# SCH_AquaMind_2026-07-25.net
KiCad netlist of a schematic drawn in EasyEDA
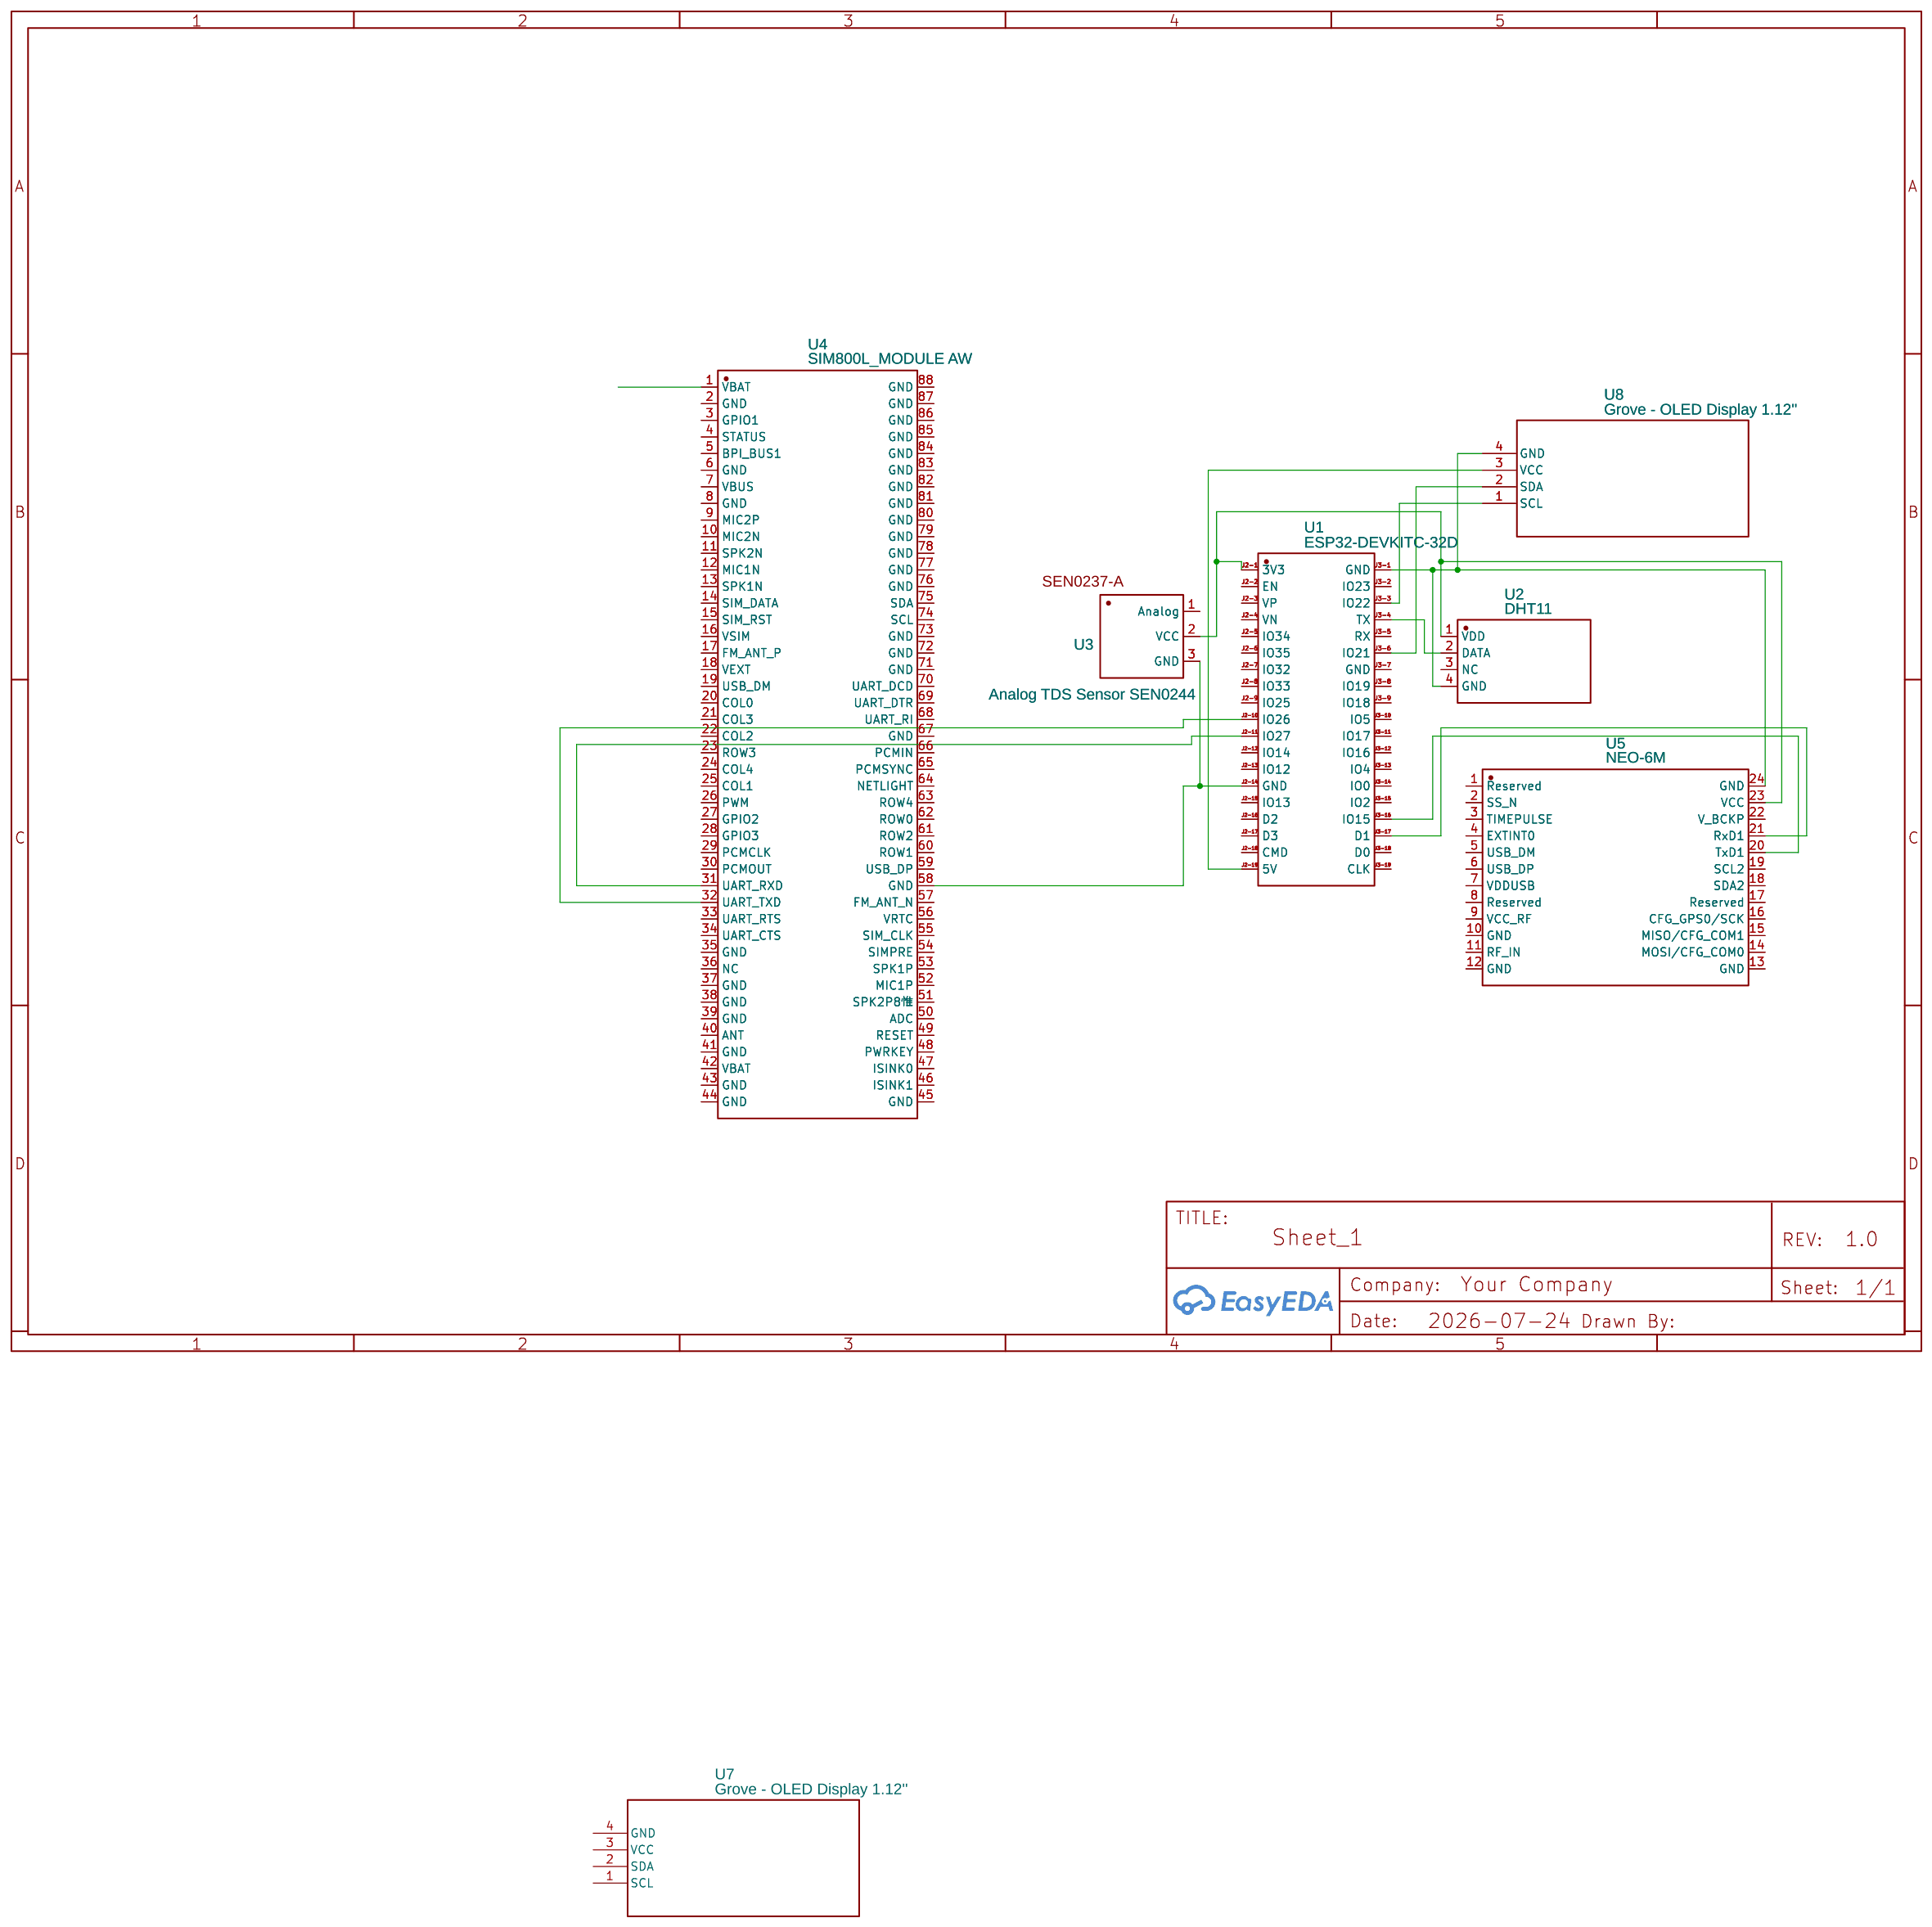
[diagram p0: schematic sheet]

(export (version "E")
  (design (tool "Eeschema 10.0.6"))
  (components
    (comp (ref "U1")
      (value "ESP32-DEVKITC-32D")
      (fields
        (field (name "Manufacturer Part") "ESP32-DevKitC-32D")
        (field (name "Manufacturer") "ESPRESSIF(乐鑫)")
      )
      (libsource (lib "") (part "ESP32-DEVKITC-32D"))
    )
    (comp (ref "U2")
      (value "DHT11")
      (fields (field (name "Manufacturer") "广州奥松"))
      (libsource (lib "") (part "DHT11"))
    )
    (comp (ref "U3")
      (value "Analog TDS Sensor SEN0244")
      (libsource (lib "") (part "Analog TDS Sensor SEN0244"))
    )
    (comp (ref "U4") (value "SIM800L_MODULE AW") (libsource (lib "") (part "SIM800L_MODULE AW")))
    (comp (ref "U5") (value "NEO-6M") (libsource (lib "") (part "NEO-6M")))
    (comp (ref "U7")
      (value "Grove - OLED Display 1.12''")
      (libsource (lib "") (part "Grove - OLED Display 1.12''"))
    )
    (comp (ref "U8")
      (value "Grove - OLED Display 1.12''")
      (libsource (lib "") (part "Grove - OLED Display 1.12''"))
    )
  )
  (nets
    (net (code "1") (name "Net-(U1-3V3)") (class "Default")
      (node (ref "U1") (pin "J2-1") (pinfunction "3V3_J2-1") (pintype "unspecified"))
      (node (ref "U2") (pin "1") (pinfunction "VDD_1") (pintype "unspecified"))
      (node (ref "U3") (pin "2") (pinfunction "VCC_2") (pintype "unspecified"))
      (node (ref "U5") (pin "23") (pinfunction "VCC_23") (pintype "unspecified"))
    )
    (net (code "2") (name "Net-(U1-5V)") (class "Default")
      (node (ref "U1") (pin "J2-19") (pinfunction "5V_J2-19") (pintype "unspecified"))
      (node (ref "U8") (pin "3") (pinfunction "VCC_3") (pintype "unspecified"))
    )
    (net (code "3") (name "Net-(U1-D1)") (class "Default")
      (node (ref "U1") (pin "J3-17") (pinfunction "D1_J3-17") (pintype "unspecified"))
      (node (ref "U5") (pin "21") (pinfunction "RxD1_21") (pintype "unspecified"))
    )
    (net (code "4") (name "Net-(U1-IO15)") (class "Default")
      (node (ref "U1") (pin "J3-16") (pinfunction "IO15_J3-16") (pintype "unspecified"))
      (node (ref "U5") (pin "20") (pinfunction "TxD1_20") (pintype "unspecified"))
    )
    (net (code "5") (name "Net-(U1-IO21)") (class "Default")
      (node (ref "U1") (pin "J3-6") (pinfunction "IO21_J3-6") (pintype "unspecified"))
      (node (ref "U8") (pin "2") (pinfunction "SDA_2") (pintype "unspecified"))
    )
    (net (code "6") (name "Net-(U1-IO22)") (class "Default")
      (node (ref "U1") (pin "J3-3") (pinfunction "IO22_J3-3") (pintype "unspecified"))
      (node (ref "U8") (pin "1") (pinfunction "SCL_1") (pintype "unspecified"))
    )
    (net (code "7") (name "Net-(U1-IO26)") (class "Default")
      (node (ref "U1") (pin "J2-10") (pinfunction "IO26_J2-10") (pintype "unspecified"))
      (node (ref "U4") (pin "32") (pinfunction "UART_TXD_32") (pintype "unspecified"))
    )
    (net (code "8") (name "Net-(U1-IO27)") (class "Default")
      (node (ref "U1") (pin "J2-11") (pinfunction "IO27_J2-11") (pintype "unspecified"))
      (node (ref "U4") (pin "31") (pinfunction "UART_RXD_31") (pintype "unspecified"))
    )
    (net (code "9") (name "Net-(U1-TX)") (class "Default")
      (node (ref "U1") (pin "J3-4") (pinfunction "TX_J3-4") (pintype "unspecified"))
      (node (ref "U2") (pin "2") (pinfunction "DATA_2") (pintype "unspecified"))
    )
    (net (code "10") (name "Net-(U2-GND)") (class "Default")
      (node (ref "U1") (pin "J3-1") (pinfunction "GND_J3-1") (pintype "unspecified"))
      (node (ref "U2") (pin "4") (pinfunction "GND_4") (pintype "unspecified"))
      (node (ref "U5") (pin "24") (pinfunction "GND_24") (pintype "unspecified"))
      (node (ref "U8") (pin "4") (pinfunction "GND_4") (pintype "unspecified"))
    )
    (net (code "11") (name "Net-(U3-GND)") (class "Default")
      (node (ref "U1") (pin "J2-14") (pinfunction "GND_J2-14") (pintype "unspecified"))
      (node (ref "U3") (pin "3") (pinfunction "GND_3") (pintype "unspecified"))
      (node (ref "U4") (pin "58") (pinfunction "GND_58") (pintype "unspecified"))
    )
    (net (code "12") (name "unconnected-(U1-CLK-PadJ3-19)") (class "Default")
      (node (ref "U1") (pin "J3-19") (pinfunction "CLK_J3-19") (pintype "unspecified"))
    )
    (net (code "13") (name "unconnected-(U1-CMD-PadJ2-18)") (class "Default")
      (node (ref "U1") (pin "J2-18") (pinfunction "CMD_J2-18") (pintype "unspecified"))
    )
    (net (code "14") (name "unconnected-(U1-D0-PadJ3-18)") (class "Default")
      (node (ref "U1") (pin "J3-18") (pinfunction "D0_J3-18") (pintype "unspecified"))
    )
    (net (code "15") (name "unconnected-(U1-D2-PadJ2-16)") (class "Default")
      (node (ref "U1") (pin "J2-16") (pinfunction "D2_J2-16") (pintype "unspecified"))
    )
    (net (code "16") (name "unconnected-(U1-D3-PadJ2-17)") (class "Default")
      (node (ref "U1") (pin "J2-17") (pinfunction "D3_J2-17") (pintype "unspecified"))
    )
    (net (code "17") (name "unconnected-(U1-EN-PadJ2-2)") (class "Default")
      (node (ref "U1") (pin "J2-2") (pinfunction "EN_J2-2") (pintype "unspecified"))
    )
    (net (code "18") (name "unconnected-(U1-GND-PadJ3-7)") (class "Default")
      (node (ref "U1") (pin "J3-7") (pinfunction "GND_J3-7") (pintype "unspecified"))
    )
    (net (code "19") (name "unconnected-(U1-IO0-PadJ3-14)") (class "Default")
      (node (ref "U1") (pin "J3-14") (pinfunction "IO0_J3-14") (pintype "unspecified"))
    )
    (net (code "20") (name "unconnected-(U1-IO2-PadJ3-15)") (class "Default")
      (node (ref "U1") (pin "J3-15") (pinfunction "IO2_J3-15") (pintype "unspecified"))
    )
    (net (code "21") (name "unconnected-(U1-IO4-PadJ3-13)") (class "Default")
      (node (ref "U1") (pin "J3-13") (pinfunction "IO4_J3-13") (pintype "unspecified"))
    )
    (net (code "22") (name "unconnected-(U1-IO5-PadJ3-10)") (class "Default")
      (node (ref "U1") (pin "J3-10") (pinfunction "IO5_J3-10") (pintype "unspecified"))
    )
    (net (code "23") (name "unconnected-(U1-IO12-PadJ2-13)") (class "Default")
      (node (ref "U1") (pin "J2-13") (pinfunction "IO12_J2-13") (pintype "unspecified"))
    )
    (net (code "24") (name "unconnected-(U1-IO13-PadJ2-15)") (class "Default")
      (node (ref "U1") (pin "J2-15") (pinfunction "IO13_J2-15") (pintype "unspecified"))
    )
    (net (code "25") (name "unconnected-(U1-IO14-PadJ2-12)") (class "Default")
      (node (ref "U1") (pin "J2-12") (pinfunction "IO14_J2-12") (pintype "unspecified"))
    )
    (net (code "26") (name "unconnected-(U1-IO16-PadJ3-12)") (class "Default")
      (node (ref "U1") (pin "J3-12") (pinfunction "IO16_J3-12") (pintype "unspecified"))
    )
    (net (code "27") (name "unconnected-(U1-IO17-PadJ3-11)") (class "Default")
      (node (ref "U1") (pin "J3-11") (pinfunction "IO17_J3-11") (pintype "unspecified"))
    )
    (net (code "28") (name "unconnected-(U1-IO18-PadJ3-9)") (class "Default")
      (node (ref "U1") (pin "J3-9") (pinfunction "IO18_J3-9") (pintype "unspecified"))
    )
    (net (code "29") (name "unconnected-(U1-IO19-PadJ3-8)") (class "Default")
      (node (ref "U1") (pin "J3-8") (pinfunction "IO19_J3-8") (pintype "unspecified"))
    )
    (net (code "30") (name "unconnected-(U1-IO23-PadJ3-2)") (class "Default")
      (node (ref "U1") (pin "J3-2") (pinfunction "IO23_J3-2") (pintype "unspecified"))
    )
    (net (code "31") (name "unconnected-(U1-IO25-PadJ2-9)") (class "Default")
      (node (ref "U1") (pin "J2-9") (pinfunction "IO25_J2-9") (pintype "unspecified"))
    )
    (net (code "32") (name "unconnected-(U1-IO32-PadJ2-7)") (class "Default")
      (node (ref "U1") (pin "J2-7") (pinfunction "IO32_J2-7") (pintype "unspecified"))
    )
    (net (code "33") (name "unconnected-(U1-IO33-PadJ2-8)") (class "Default")
      (node (ref "U1") (pin "J2-8") (pinfunction "IO33_J2-8") (pintype "unspecified"))
    )
    (net (code "34") (name "unconnected-(U1-IO34-PadJ2-5)") (class "Default")
      (node (ref "U1") (pin "J2-5") (pinfunction "IO34_J2-5") (pintype "unspecified"))
    )
    (net (code "35") (name "unconnected-(U1-IO35-PadJ2-6)") (class "Default")
      (node (ref "U1") (pin "J2-6") (pinfunction "IO35_J2-6") (pintype "unspecified"))
    )
    (net (code "36") (name "unconnected-(U1-RX-PadJ3-5)") (class "Default")
      (node (ref "U1") (pin "J3-5") (pinfunction "RX_J3-5") (pintype "unspecified"))
    )
    (net (code "37") (name "unconnected-(U1-VN-PadJ2-4)") (class "Default")
      (node (ref "U1") (pin "J2-4") (pinfunction "VN_J2-4") (pintype "unspecified"))
    )
    (net (code "38") (name "unconnected-(U1-VP-PadJ2-3)") (class "Default")
      (node (ref "U1") (pin "J2-3") (pinfunction "VP_J2-3") (pintype "unspecified"))
    )
    (net (code "39") (name "unconnected-(U2-NC-Pad3)") (class "Default")
      (node (ref "U2") (pin "3") (pinfunction "NC_3") (pintype "unspecified"))
    )
    (net (code "40") (name "unconnected-(U3-Analog-Pad1)") (class "Default")
      (node (ref "U3") (pin "1") (pinfunction "Analog_1") (pintype "unspecified"))
    )
    (net (code "41") (name "unconnected-(U4-ADC-Pad50)") (class "Default")
      (node (ref "U4") (pin "50") (pinfunction "ADC_50") (pintype "unspecified"))
    )
    (net (code "42") (name "unconnected-(U4-ANT-Pad40)") (class "Default")
      (node (ref "U4") (pin "40") (pinfunction "ANT_40") (pintype "unspecified"))
    )
    (net (code "43") (name "unconnected-(U4-BPI_BUS1-Pad5)") (class "Default")
      (node (ref "U4") (pin "5") (pinfunction "BPI_BUS1_5") (pintype "unspecified"))
    )
    (net (code "44") (name "unconnected-(U4-COL0-Pad20)") (class "Default")
      (node (ref "U4") (pin "20") (pinfunction "COL0_20") (pintype "unspecified"))
    )
    (net (code "45") (name "unconnected-(U4-COL1-Pad25)") (class "Default")
      (node (ref "U4") (pin "25") (pinfunction "COL1_25") (pintype "unspecified"))
    )
    (net (code "46") (name "unconnected-(U4-COL2-Pad22)") (class "Default")
      (node (ref "U4") (pin "22") (pinfunction "COL2_22") (pintype "unspecified"))
    )
    (net (code "47") (name "unconnected-(U4-COL3-Pad21)") (class "Default")
      (node (ref "U4") (pin "21") (pinfunction "COL3_21") (pintype "unspecified"))
    )
    (net (code "48") (name "unconnected-(U4-COL4-Pad24)") (class "Default")
      (node (ref "U4") (pin "24") (pinfunction "COL4_24") (pintype "unspecified"))
    )
    (net (code "49") (name "unconnected-(U4-FM_ANT_N-Pad57)") (class "Default")
      (node (ref "U4") (pin "57") (pinfunction "FM_ANT_N_57") (pintype "unspecified"))
    )
    (net (code "50") (name "unconnected-(U4-FM_ANT_P-Pad17)") (class "Default")
      (node (ref "U4") (pin "17") (pinfunction "FM_ANT_P_17") (pintype "unspecified"))
    )
    (net (code "51") (name "unconnected-(U4-GND-Pad2)") (class "Default")
      (node (ref "U4") (pin "2") (pinfunction "GND_2") (pintype "unspecified"))
    )
    (net (code "52") (name "unconnected-(U4-GND-Pad6)") (class "Default")
      (node (ref "U4") (pin "6") (pinfunction "GND_6") (pintype "unspecified"))
    )
    (net (code "53") (name "unconnected-(U4-GND-Pad8)") (class "Default")
      (node (ref "U4") (pin "8") (pinfunction "GND_8") (pintype "unspecified"))
    )
    (net (code "54") (name "unconnected-(U4-GND-Pad35)") (class "Default")
      (node (ref "U4") (pin "35") (pinfunction "GND_35") (pintype "unspecified"))
    )
    (net (code "55") (name "unconnected-(U4-GND-Pad37)") (class "Default")
      (node (ref "U4") (pin "37") (pinfunction "GND_37") (pintype "unspecified"))
    )
    (net (code "56") (name "unconnected-(U4-GND-Pad38)") (class "Default")
      (node (ref "U4") (pin "38") (pinfunction "GND_38") (pintype "unspecified"))
    )
    (net (code "57") (name "unconnected-(U4-GND-Pad39)") (class "Default")
      (node (ref "U4") (pin "39") (pinfunction "GND_39") (pintype "unspecified"))
    )
    (net (code "58") (name "unconnected-(U4-GND-Pad41)") (class "Default")
      (node (ref "U4") (pin "41") (pinfunction "GND_41") (pintype "unspecified"))
    )
    (net (code "59") (name "unconnected-(U4-GND-Pad43)") (class "Default")
      (node (ref "U4") (pin "43") (pinfunction "GND_43") (pintype "unspecified"))
    )
    (net (code "60") (name "unconnected-(U4-GND-Pad44)") (class "Default")
      (node (ref "U4") (pin "44") (pinfunction "GND_44") (pintype "unspecified"))
    )
    (net (code "61") (name "unconnected-(U4-GND-Pad45)") (class "Default")
      (node (ref "U4") (pin "45") (pinfunction "GND_45") (pintype "unspecified"))
    )
    (net (code "62") (name "unconnected-(U4-GND-Pad67)") (class "Default")
      (node (ref "U4") (pin "67") (pinfunction "GND_67") (pintype "unspecified"))
    )
    (net (code "63") (name "unconnected-(U4-GND-Pad71)") (class "Default")
      (node (ref "U4") (pin "71") (pinfunction "GND_71") (pintype "unspecified"))
    )
    (net (code "64") (name "unconnected-(U4-GND-Pad72)") (class "Default")
      (node (ref "U4") (pin "72") (pinfunction "GND_72") (pintype "unspecified"))
    )
    (net (code "65") (name "unconnected-(U4-GND-Pad73)") (class "Default")
      (node (ref "U4") (pin "73") (pinfunction "GND_73") (pintype "unspecified"))
    )
    (net (code "66") (name "unconnected-(U4-GND-Pad76)") (class "Default")
      (node (ref "U4") (pin "76") (pinfunction "GND_76") (pintype "unspecified"))
    )
    (net (code "67") (name "unconnected-(U4-GND-Pad77)") (class "Default")
      (node (ref "U4") (pin "77") (pinfunction "GND_77") (pintype "unspecified"))
    )
    (net (code "68") (name "unconnected-(U4-GND-Pad78)") (class "Default")
      (node (ref "U4") (pin "78") (pinfunction "GND_78") (pintype "unspecified"))
    )
    (net (code "69") (name "unconnected-(U4-GND-Pad79)") (class "Default")
      (node (ref "U4") (pin "79") (pinfunction "GND_79") (pintype "unspecified"))
    )
    (net (code "70") (name "unconnected-(U4-GND-Pad80)") (class "Default")
      (node (ref "U4") (pin "80") (pinfunction "GND_80") (pintype "unspecified"))
    )
    (net (code "71") (name "unconnected-(U4-GND-Pad81)") (class "Default")
      (node (ref "U4") (pin "81") (pinfunction "GND_81") (pintype "unspecified"))
    )
    (net (code "72") (name "unconnected-(U4-GND-Pad82)") (class "Default")
      (node (ref "U4") (pin "82") (pinfunction "GND_82") (pintype "unspecified"))
    )
    (net (code "73") (name "unconnected-(U4-GND-Pad83)") (class "Default")
      (node (ref "U4") (pin "83") (pinfunction "GND_83") (pintype "unspecified"))
    )
    (net (code "74") (name "unconnected-(U4-GND-Pad84)") (class "Default")
      (node (ref "U4") (pin "84") (pinfunction "GND_84") (pintype "unspecified"))
    )
    (net (code "75") (name "unconnected-(U4-GND-Pad85)") (class "Default")
      (node (ref "U4") (pin "85") (pinfunction "GND_85") (pintype "unspecified"))
    )
    (net (code "76") (name "unconnected-(U4-GND-Pad86)") (class "Default")
      (node (ref "U4") (pin "86") (pinfunction "GND_86") (pintype "unspecified"))
    )
    (net (code "77") (name "unconnected-(U4-GND-Pad87)") (class "Default")
      (node (ref "U4") (pin "87") (pinfunction "GND_87") (pintype "unspecified"))
    )
    (net (code "78") (name "unconnected-(U4-GND-Pad88)") (class "Default")
      (node (ref "U4") (pin "88") (pinfunction "GND_88") (pintype "unspecified"))
    )
    (net (code "79") (name "unconnected-(U4-GPIO1-Pad3)") (class "Default")
      (node (ref "U4") (pin "3") (pinfunction "GPIO1_3") (pintype "unspecified"))
    )
    (net (code "80") (name "unconnected-(U4-GPIO2-Pad27)") (class "Default")
      (node (ref "U4") (pin "27") (pinfunction "GPIO2_27") (pintype "unspecified"))
    )
    (net (code "81") (name "unconnected-(U4-GPIO3-Pad28)") (class "Default")
      (node (ref "U4") (pin "28") (pinfunction "GPIO3_28") (pintype "unspecified"))
    )
    (net (code "82") (name "unconnected-(U4-ISINK0-Pad47)") (class "Default")
      (node (ref "U4") (pin "47") (pinfunction "ISINK0_47") (pintype "unspecified"))
    )
    (net (code "83") (name "unconnected-(U4-ISINK1-Pad46)") (class "Default")
      (node (ref "U4") (pin "46") (pinfunction "ISINK1_46") (pintype "unspecified"))
    )
    (net (code "84") (name "unconnected-(U4-MIC1N-Pad12)") (class "Default")
      (node (ref "U4") (pin "12") (pinfunction "MIC1N_12") (pintype "unspecified"))
    )
    (net (code "85") (name "unconnected-(U4-MIC1P-Pad52)") (class "Default")
      (node (ref "U4") (pin "52") (pinfunction "MIC1P_52") (pintype "unspecified"))
    )
    (net (code "86") (name "unconnected-(U4-MIC2N-Pad10)") (class "Default")
      (node (ref "U4") (pin "10") (pinfunction "MIC2N_10") (pintype "unspecified"))
    )
    (net (code "87") (name "unconnected-(U4-MIC2P-Pad9)") (class "Default")
      (node (ref "U4") (pin "9") (pinfunction "MIC2P_9") (pintype "unspecified"))
    )
    (net (code "88") (name "unconnected-(U4-NC-Pad36)") (class "Default")
      (node (ref "U4") (pin "36") (pinfunction "NC_36") (pintype "unspecified"))
    )
    (net (code "89") (name "unconnected-(U4-NETLIGHT-Pad64)") (class "Default")
      (node (ref "U4") (pin "64") (pinfunction "NETLIGHT_64") (pintype "unspecified"))
    )
    (net (code "90") (name "unconnected-(U4-PCMCLK-Pad29)") (class "Default")
      (node (ref "U4") (pin "29") (pinfunction "PCMCLK_29") (pintype "unspecified"))
    )
    (net (code "91") (name "unconnected-(U4-PCMIN-Pad66)") (class "Default")
      (node (ref "U4") (pin "66") (pinfunction "PCMIN_66") (pintype "unspecified"))
    )
    (net (code "92") (name "unconnected-(U4-PCMOUT-Pad30)") (class "Default")
      (node (ref "U4") (pin "30") (pinfunction "PCMOUT_30") (pintype "unspecified"))
    )
    (net (code "93") (name "unconnected-(U4-PCMSYNC-Pad65)") (class "Default")
      (node (ref "U4") (pin "65") (pinfunction "PCMSYNC_65") (pintype "unspecified"))
    )
    (net (code "94") (name "unconnected-(U4-PWM-Pad26)") (class "Default")
      (node (ref "U4") (pin "26") (pinfunction "PWM_26") (pintype "unspecified"))
    )
    (net (code "95") (name "unconnected-(U4-PWRKEY-Pad48)") (class "Default")
      (node (ref "U4") (pin "48") (pinfunction "PWRKEY_48") (pintype "unspecified"))
    )
    (net (code "96") (name "unconnected-(U4-RESET-Pad49)") (class "Default")
      (node (ref "U4") (pin "49") (pinfunction "RESET_49") (pintype "unspecified"))
    )
    (net (code "97") (name "unconnected-(U4-ROW0-Pad62)") (class "Default")
      (node (ref "U4") (pin "62") (pinfunction "ROW0_62") (pintype "unspecified"))
    )
    (net (code "98") (name "unconnected-(U4-ROW1-Pad60)") (class "Default")
      (node (ref "U4") (pin "60") (pinfunction "ROW1_60") (pintype "unspecified"))
    )
    (net (code "99") (name "unconnected-(U4-ROW2-Pad61)") (class "Default")
      (node (ref "U4") (pin "61") (pinfunction "ROW2_61") (pintype "unspecified"))
    )
    (net (code "100") (name "unconnected-(U4-ROW3-Pad23)") (class "Default")
      (node (ref "U4") (pin "23") (pinfunction "ROW3_23") (pintype "unspecified"))
    )
    (net (code "101") (name "unconnected-(U4-ROW4-Pad63)") (class "Default")
      (node (ref "U4") (pin "63") (pinfunction "ROW4_63") (pintype "unspecified"))
    )
    (net (code "102") (name "unconnected-(U4-SCL-Pad74)") (class "Default")
      (node (ref "U4") (pin "74") (pinfunction "SCL_74") (pintype "unspecified"))
    )
    (net (code "103") (name "unconnected-(U4-SDA-Pad75)") (class "Default")
      (node (ref "U4") (pin "75") (pinfunction "SDA_75") (pintype "unspecified"))
    )
    (net (code "104") (name "unconnected-(U4-SIMPRE-Pad54)") (class "Default")
      (node (ref "U4") (pin "54") (pinfunction "SIMPRE_54") (pintype "unspecified"))
    )
    (net (code "105") (name "unconnected-(U4-SIM_CLK-Pad55)") (class "Default")
      (node (ref "U4") (pin "55") (pinfunction "SIM_CLK_55") (pintype "unspecified"))
    )
    (net (code "106") (name "unconnected-(U4-SIM_DATA-Pad14)") (class "Default")
      (node (ref "U4") (pin "14") (pinfunction "SIM_DATA_14") (pintype "unspecified"))
    )
    (net (code "107") (name "unconnected-(U4-SIM_RST-Pad15)") (class "Default")
      (node (ref "U4") (pin "15") (pinfunction "SIM_RST_15") (pintype "unspecified"))
    )
    (net (code "108") (name "unconnected-(U4-SPK1N-Pad13)") (class "Default")
      (node (ref "U4") (pin "13") (pinfunction "SPK1N_13") (pintype "unspecified"))
    )
    (net (code "109") (name "unconnected-(U4-SPK1P-Pad53)") (class "Default")
      (node (ref "U4") (pin "53") (pinfunction "SPK1P_53") (pintype "unspecified"))
    )
    (net (code "110") (name "unconnected-(U4-SPK2N-Pad11)") (class "Default")
      (node (ref "U4") (pin "11") (pinfunction "SPK2N_11") (pintype "unspecified"))
    )
    (net (code "111") (name "unconnected-(U4-SPK2P8惟-Pad51)") (class "Default")
      (node (ref "U4") (pin "51") (pinfunction "SPK2P8惟_51") (pintype "unspecified"))
    )
    (net (code "112") (name "unconnected-(U4-STATUS-Pad4)") (class "Default")
      (node (ref "U4") (pin "4") (pinfunction "STATUS_4") (pintype "unspecified"))
    )
    (net (code "113") (name "unconnected-(U4-UART_CTS-Pad34)") (class "Default")
      (node (ref "U4") (pin "34") (pinfunction "UART_CTS_34") (pintype "unspecified"))
    )
    (net (code "114") (name "unconnected-(U4-UART_DCD-Pad70)") (class "Default")
      (node (ref "U4") (pin "70") (pinfunction "UART_DCD_70") (pintype "unspecified"))
    )
    (net (code "115") (name "unconnected-(U4-UART_DTR-Pad69)") (class "Default")
      (node (ref "U4") (pin "69") (pinfunction "UART_DTR_69") (pintype "unspecified"))
    )
    (net (code "116") (name "unconnected-(U4-UART_RI-Pad68)") (class "Default")
      (node (ref "U4") (pin "68") (pinfunction "UART_RI_68") (pintype "unspecified"))
    )
    (net (code "117") (name "unconnected-(U4-UART_RTS-Pad33)") (class "Default")
      (node (ref "U4") (pin "33") (pinfunction "UART_RTS_33") (pintype "unspecified"))
    )
    (net (code "118") (name "unconnected-(U4-USB_DM-Pad19)") (class "Default")
      (node (ref "U4") (pin "19") (pinfunction "USB_DM_19") (pintype "unspecified"))
    )
    (net (code "119") (name "unconnected-(U4-USB_DP-Pad59)") (class "Default")
      (node (ref "U4") (pin "59") (pinfunction "USB_DP_59") (pintype "unspecified"))
    )
    (net (code "120") (name "unconnected-(U4-VBAT-Pad1)") (class "Default")
      (node (ref "U4") (pin "1") (pinfunction "VBAT_1") (pintype "unspecified"))
    )
    (net (code "121") (name "unconnected-(U4-VBAT-Pad42)") (class "Default")
      (node (ref "U4") (pin "42") (pinfunction "VBAT_42") (pintype "unspecified"))
    )
    (net (code "122") (name "unconnected-(U4-VBUS-Pad7)") (class "Default")
      (node (ref "U4") (pin "7") (pinfunction "VBUS_7") (pintype "unspecified"))
    )
    (net (code "123") (name "unconnected-(U4-VEXT-Pad18)") (class "Default")
      (node (ref "U4") (pin "18") (pinfunction "VEXT_18") (pintype "unspecified"))
    )
    (net (code "124") (name "unconnected-(U4-VRTC-Pad56)") (class "Default")
      (node (ref "U4") (pin "56") (pinfunction "VRTC_56") (pintype "unspecified"))
    )
    (net (code "125") (name "unconnected-(U4-VSIM-Pad16)") (class "Default")
      (node (ref "U4") (pin "16") (pinfunction "VSIM_16") (pintype "unspecified"))
    )
    (net (code "126") (name "unconnected-(U5-CFG_GPS0{slash}SCK-Pad16)") (class "Default")
      (node (ref "U5") (pin "16") (pinfunction "CFG_GPS0/SCK_16") (pintype "unspecified"))
    )
    (net (code "127") (name "unconnected-(U5-EXTINT0-Pad4)") (class "Default")
      (node (ref "U5") (pin "4") (pinfunction "EXTINT0_4") (pintype "unspecified"))
    )
    (net (code "128") (name "unconnected-(U5-GND-Pad10)") (class "Default")
      (node (ref "U5") (pin "10") (pinfunction "GND_10") (pintype "unspecified"))
    )
    (net (code "129") (name "unconnected-(U5-GND-Pad12)") (class "Default")
      (node (ref "U5") (pin "12") (pinfunction "GND_12") (pintype "unspecified"))
    )
    (net (code "130") (name "unconnected-(U5-GND-Pad13)") (class "Default")
      (node (ref "U5") (pin "13") (pinfunction "GND_13") (pintype "unspecified"))
    )
    (net (code "131") (name "unconnected-(U5-MISO{slash}CFG_COM1-Pad15)") (class "Default")
      (node (ref "U5") (pin "15") (pinfunction "MISO/CFG_COM1_15") (pintype "unspecified"))
    )
    (net (code "132") (name "unconnected-(U5-MOSI{slash}CFG_COM0-Pad14)") (class "Default")
      (node (ref "U5") (pin "14") (pinfunction "MOSI/CFG_COM0_14") (pintype "unspecified"))
    )
    (net (code "133") (name "unconnected-(U5-RF_IN-Pad11)") (class "Default")
      (node (ref "U5") (pin "11") (pinfunction "RF_IN_11") (pintype "unspecified"))
    )
    (net (code "134") (name "unconnected-(U5-Reserved-Pad1)") (class "Default")
      (node (ref "U5") (pin "1") (pinfunction "Reserved_1") (pintype "unspecified"))
    )
    (net (code "135") (name "unconnected-(U5-Reserved-Pad8)") (class "Default")
      (node (ref "U5") (pin "8") (pinfunction "Reserved_8") (pintype "unspecified"))
    )
    (net (code "136") (name "unconnected-(U5-Reserved-Pad17)") (class "Default")
      (node (ref "U5") (pin "17") (pinfunction "Reserved_17") (pintype "unspecified"))
    )
    (net (code "137") (name "unconnected-(U5-SCL2-Pad19)") (class "Default")
      (node (ref "U5") (pin "19") (pinfunction "SCL2_19") (pintype "unspecified"))
    )
    (net (code "138") (name "unconnected-(U5-SDA2-Pad18)") (class "Default")
      (node (ref "U5") (pin "18") (pinfunction "SDA2_18") (pintype "unspecified"))
    )
    (net (code "139") (name "unconnected-(U5-SS_N-Pad2)") (class "Default")
      (node (ref "U5") (pin "2") (pinfunction "SS_N_2") (pintype "unspecified"))
    )
    (net (code "140") (name "unconnected-(U5-TIMEPULSE-Pad3)") (class "Default")
      (node (ref "U5") (pin "3") (pinfunction "TIMEPULSE_3") (pintype "unspecified"))
    )
    (net (code "141") (name "unconnected-(U5-USB_DM-Pad5)") (class "Default")
      (node (ref "U5") (pin "5") (pinfunction "USB_DM_5") (pintype "unspecified"))
    )
    (net (code "142") (name "unconnected-(U5-USB_DP-Pad6)") (class "Default")
      (node (ref "U5") (pin "6") (pinfunction "USB_DP_6") (pintype "unspecified"))
    )
    (net (code "143") (name "unconnected-(U5-VCC_RF-Pad9)") (class "Default")
      (node (ref "U5") (pin "9") (pinfunction "VCC_RF_9") (pintype "unspecified"))
    )
    (net (code "144") (name "unconnected-(U5-VDDUSB-Pad7)") (class "Default")
      (node (ref "U5") (pin "7") (pinfunction "VDDUSB_7") (pintype "unspecified"))
    )
    (net (code "145") (name "unconnected-(U5-V_BCKP-Pad22)") (class "Default")
      (node (ref "U5") (pin "22") (pinfunction "V_BCKP_22") (pintype "unspecified"))
    )
    (net (code "146") (name "unconnected-(U7-GND-Pad4)") (class "Default")
      (node (ref "U7") (pin "4") (pinfunction "GND_4") (pintype "unspecified"))
    )
    (net (code "147") (name "unconnected-(U7-SCL-Pad1)") (class "Default")
      (node (ref "U7") (pin "1") (pinfunction "SCL_1") (pintype "unspecified"))
    )
    (net (code "148") (name "unconnected-(U7-SDA-Pad2)") (class "Default")
      (node (ref "U7") (pin "2") (pinfunction "SDA_2") (pintype "unspecified"))
    )
    (net (code "149") (name "unconnected-(U7-VCC-Pad3)") (class "Default")
      (node (ref "U7") (pin "3") (pinfunction "VCC_3") (pintype "unspecified"))
    )
  )
)
